# stb.net
KiCad netlist of a schematic drawn in EAGLE
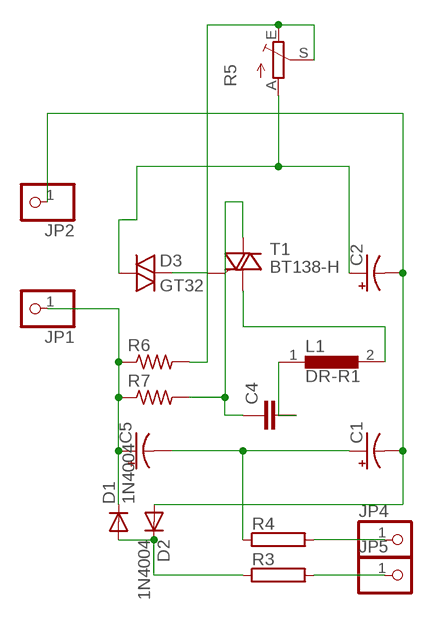
[diagram p0: schematic, sheet 1]

(export (version "E")
  (design (tool "Eeschema 10.0.6"))
  (components
    (comp (ref "C1")
      (value "CPOL-USE7.5-16")
      (footprint "eagle-import:E7,5-16")
      (libsource (lib "eagle-import") (part "CPOL-USE7.5-16"))
    )
    (comp (ref "C2")
      (value "CPOL-USE7.5-16")
      (footprint "eagle-import:E7,5-16")
      (libsource (lib "eagle-import") (part "CPOL-USE7.5-16"))
    )
    (comp (ref "C4")
      (value "C10/5")
      (footprint "eagle-import:C10B5")
      (libsource (lib "eagle-import") (part "C10/5"))
    )
    (comp (ref "C5")
      (value "CPOL-USE7.5-16")
      (footprint "eagle-import:E7,5-16")
      (libsource (lib "eagle-import") (part "CPOL-USE7.5-16"))
    )
    (comp (ref "D1")
      (value "1N4004")
      (footprint "eagle-import:DO41-10")
      (libsource (lib "eagle-import") (part "1N4004"))
    )
    (comp (ref "D2")
      (value "1N4004")
      (footprint "eagle-import:DO41-10")
      (libsource (lib "eagle-import") (part "1N4004"))
    )
    (comp (ref "D3")
      (value "GT32")
      (footprint "eagle-import:GT32")
      (libsource (lib "eagle-import") (part "GT32"))
    )
    (comp (ref "JP1")
      (value "PINHD-1X1")
      (footprint "eagle-import:1X01")
      (libsource (lib "eagle-import") (part "PINHD-1X1"))
    )
    (comp (ref "JP2")
      (value "PINHD-1X1")
      (footprint "eagle-import:1X01")
      (libsource (lib "eagle-import") (part "PINHD-1X1"))
    )
    (comp (ref "JP4")
      (value "PINHD-1X1")
      (footprint "eagle-import:1X01")
      (libsource (lib "eagle-import") (part "PINHD-1X1"))
    )
    (comp (ref "JP5")
      (value "PINHD-1X1")
      (footprint "eagle-import:1X01")
      (libsource (lib "eagle-import") (part "PINHD-1X1"))
    )
    (comp (ref "L1")
      (value "DR-R1")
      (footprint "eagle-import:DR-R1")
      (libsource (lib "eagle-import") (part "DR-R1"))
    )
    (comp (ref "R3")
      (value "RKWP336")
      (footprint "eagle-import:KWP336")
      (libsource (lib "eagle-import") (part "RKWP336"))
    )
    (comp (ref "R4")
      (value "RKWP336")
      (footprint "eagle-import:KWP336")
      (libsource (lib "eagle-import") (part "RKWP336"))
    )
    (comp (ref "R5")
      (value "TRIM_EU-LI10")
      (footprint "eagle-import:LI10")
      (libsource (lib "eagle-import") (part "TRIM_EU-LI10"))
    )
    (comp (ref "R6")
      (value "R-US_0207/7")
      (footprint "eagle-import:0207_7")
      (libsource (lib "eagle-import") (part "R-US_0207/7"))
    )
    (comp (ref "R7")
      (value "R-US_0207/7")
      (footprint "eagle-import:0207_7")
      (libsource (lib "eagle-import") (part "R-US_0207/7"))
    )
    (comp (ref "T1")
      (value "BT138-H")
      (footprint "eagle-import:TO220BH")
      (libsource (lib "eagle-import") (part "BT138-H"))
    )
  )
  (nets
    (net (code "1") (name "Net-(C1-Pad+)") (class "Default")
      (node (ref "C1") (pin "+") (pinfunction "+_+") (pintype "passive"))
      (node (ref "C5") (pin "-") (pinfunction "-_-") (pintype "passive"))
      (node (ref "R4") (pin "1") (pinfunction "1_1") (pintype "passive"))
    )
    (net (code "2") (name "Net-(C1-Pad-)") (class "Default")
      (node (ref "C1") (pin "-") (pinfunction "-_-") (pintype "passive"))
      (node (ref "C2") (pin "-") (pinfunction "-_-") (pintype "passive"))
      (node (ref "D2") (pin "A") (pinfunction "A_A") (pintype "passive"))
      (node (ref "JP2") (pin "1") (pinfunction "1_1") (pintype "passive"))
    )
    (net (code "3") (name "Net-(C2-Pad+)") (class "Default")
      (node (ref "C2") (pin "+") (pinfunction "+_+") (pintype "passive"))
      (node (ref "D3") (pin "1") (pinfunction "1_1") (pintype "passive"))
      (node (ref "R5") (pin "A") (pinfunction "A_A") (pintype "passive"))
    )
    (net (code "4") (name "Net-(C4-Pad2)") (class "Default")
      (node (ref "C4") (pin "2") (pinfunction "2_2") (pintype "passive"))
      (node (ref "L1") (pin "1") (pinfunction "1_1") (pintype "passive"))
    )
    (net (code "5") (name "Net-(C5-Pad+)") (class "Default")
      (node (ref "C5") (pin "+") (pinfunction "+_+") (pintype "passive"))
      (node (ref "D1") (pin "C") (pinfunction "C_C") (pintype "passive"))
      (node (ref "JP1") (pin "1") (pinfunction "1_1") (pintype "passive"))
      (node (ref "R6") (pin "1") (pinfunction "1_1") (pintype "passive"))
      (node (ref "R7") (pin "1") (pinfunction "1_1") (pintype "passive"))
    )
    (net (code "6") (name "Net-(D1-PadA)") (class "Default")
      (node (ref "D1") (pin "A") (pinfunction "A_A") (pintype "passive"))
      (node (ref "D2") (pin "C") (pinfunction "C_C") (pintype "passive"))
      (node (ref "R3") (pin "1") (pinfunction "1_1") (pintype "passive"))
    )
    (net (code "7") (name "Net-(D3-Pad2)") (class "Default")
      (node (ref "D3") (pin "2") (pinfunction "2_2") (pintype "passive"))
      (node (ref "T1") (pin "G") (pinfunction "G_G") (pintype "passive"))
    )
    (net (code "8") (name "Net-(JP4-Pad1)") (class "Default")
      (node (ref "JP4") (pin "1") (pinfunction "1_1") (pintype "passive"))
      (node (ref "R4") (pin "2") (pinfunction "2_2") (pintype "passive"))
    )
    (net (code "9") (name "Net-(JP5-Pad1)") (class "Default")
      (node (ref "JP5") (pin "1") (pinfunction "1_1") (pintype "passive"))
      (node (ref "R3") (pin "2") (pinfunction "2_2") (pintype "passive"))
    )
    (net (code "10") (name "Net-(R5-PadE)") (class "Default")
      (node (ref "R5") (pin "E") (pinfunction "E_E") (pintype "passive"))
      (node (ref "R5") (pin "S") (pinfunction "S_S") (pintype "passive"))
      (node (ref "R6") (pin "2") (pinfunction "2_2") (pintype "passive"))
    )
    (net (code "11") (name "Net-(T1-A1)") (class "Default")
      (node (ref "L1") (pin "2") (pinfunction "2_2") (pintype "passive"))
      (node (ref "T1") (pin "T1") (pinfunction "A1_T1") (pintype "passive"))
    )
    (net (code "12") (name "Net-(T1-A2)") (class "Default")
      (node (ref "C4") (pin "1") (pinfunction "1_1") (pintype "passive"))
      (node (ref "R7") (pin "2") (pinfunction "2_2") (pintype "passive"))
      (node (ref "T1") (pin "T2") (pinfunction "A2_T2") (pintype "passive"))
    )
  )
)
